# Definitivo.net
KiCad netlist of a schematic drawn in EAGLE
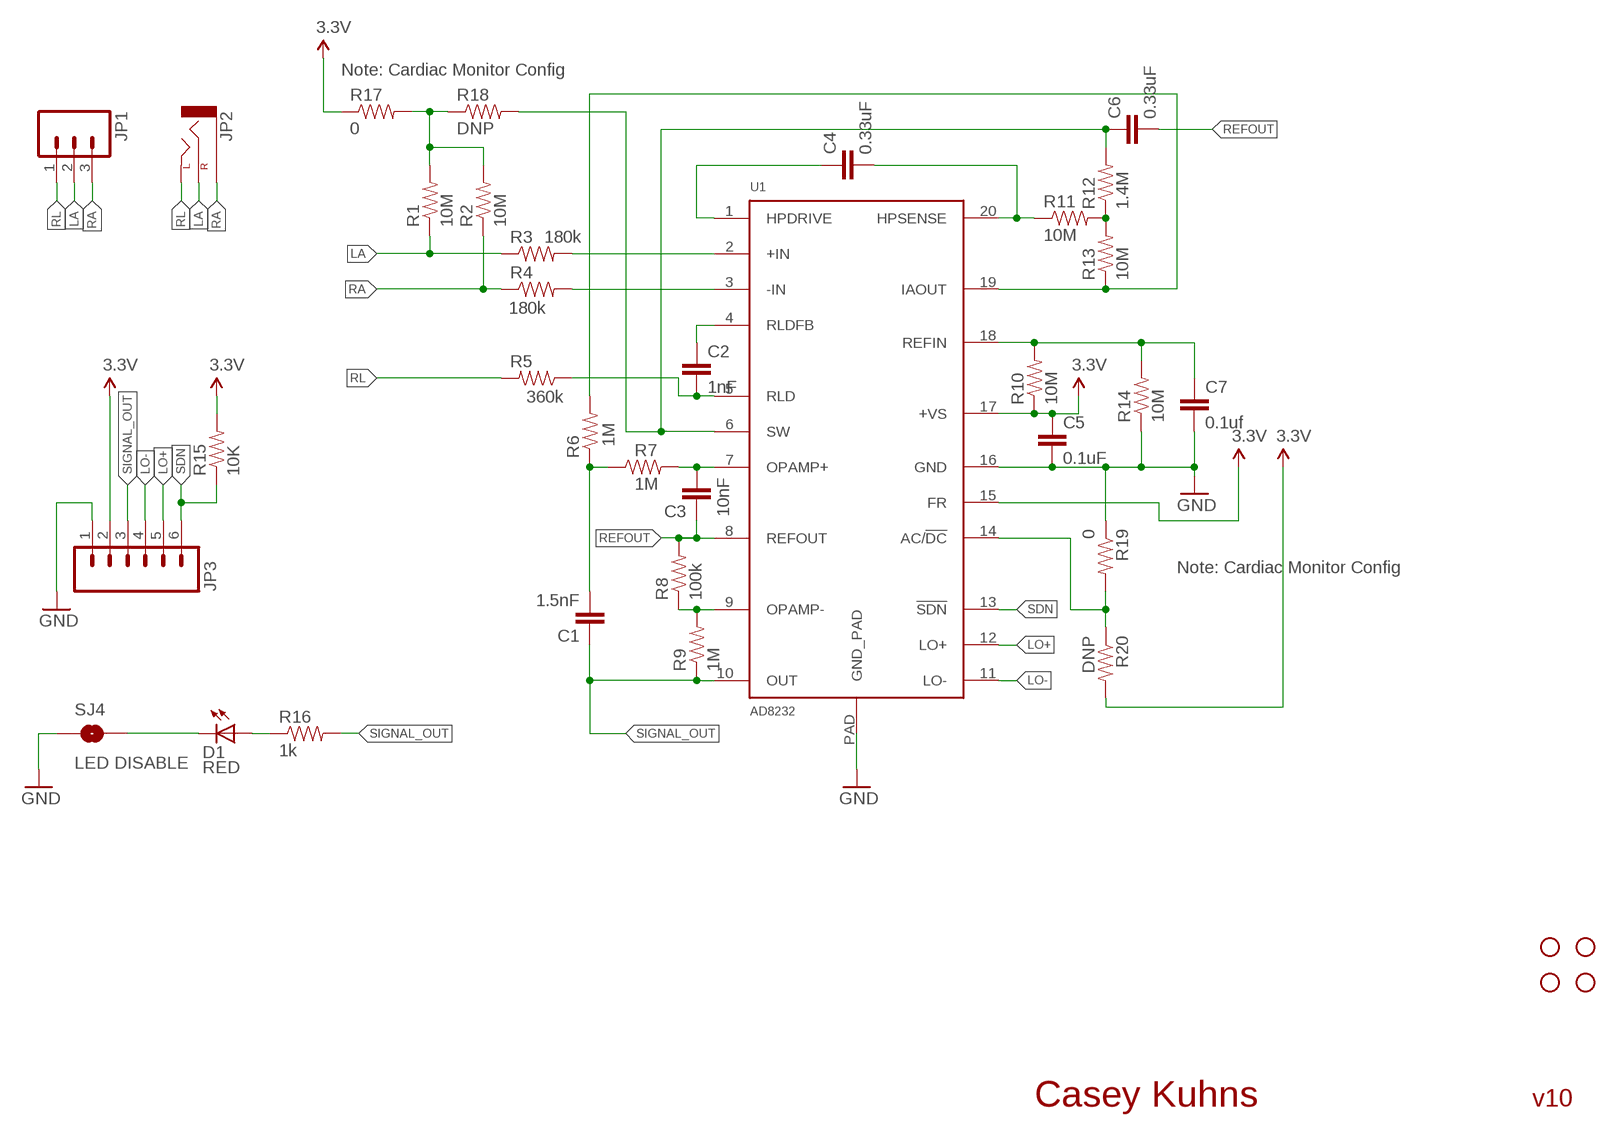
[diagram p0: schematic, sheet 1]

(export (version "E")
  (design (tool "Eeschema 10.0.6"))
  (components
    (comp (ref "C1")
      (value "1.5nF")
      (footprint "eagle-import:0603-CAP")
      (libsource (lib "eagle-import") (part "CAP0603-CAP"))
    )
    (comp (ref "C2")
      (value "1nF")
      (footprint "eagle-import:0603-CAP")
      (libsource (lib "eagle-import") (part "CAP0603-CAP"))
    )
    (comp (ref "C3")
      (value "10nF")
      (footprint "eagle-import:0603-CAP")
      (libsource (lib "eagle-import") (part "CAP0603-CAP"))
    )
    (comp (ref "C4")
      (value "0.33uF")
      (footprint "eagle-import:0805")
      (libsource (lib "eagle-import") (part "CAP0805"))
    )
    (comp (ref "C5")
      (value "0.1uF")
      (footprint "eagle-import:0603-CAP")
      (libsource (lib "eagle-import") (part "CAP0603-CAP"))
    )
    (comp (ref "C6")
      (value "0.33uF")
      (footprint "eagle-import:0805")
      (libsource (lib "eagle-import") (part "CAP0805"))
    )
    (comp (ref "C7")
      (value "0.1uf")
      (footprint "eagle-import:0603-CAP")
      (libsource (lib "eagle-import") (part "CAP0603-CAP"))
    )
    (comp (ref "D1")
      (value "RED")
      (footprint "eagle-import:LED-0603")
      (libsource (lib "eagle-import") (part "LED-RED0603"))
    )
    (comp (ref "JP1")
      (value "M03PTH")
      (footprint "eagle-import:1X03")
      (libsource (lib "eagle-import") (part "M03PTH"))
    )
    (comp (ref "JP2")
      (value "AUDIO-JACKSMD2")
      (footprint "eagle-import:AUDIO-JACK-3.5MM-SMD")
      (libsource (lib "eagle-import") (part "AUDIO-JACKSMD2"))
    )
    (comp (ref "JP3")
      (value "M06SIP")
      (footprint "eagle-import:1X06")
      (libsource (lib "eagle-import") (part "M06SIP"))
    )
    (comp (ref "R1")
      (value "10M")
      (footprint "eagle-import:0603-RES")
      (libsource (lib "eagle-import") (part "RESISTOR0603-RES"))
    )
    (comp (ref "R2")
      (value "10M")
      (footprint "eagle-import:0603-RES")
      (libsource (lib "eagle-import") (part "RESISTOR0603-RES"))
    )
    (comp (ref "R3")
      (value "180k")
      (footprint "eagle-import:0603-RES")
      (libsource (lib "eagle-import") (part "RESISTOR0603-RES"))
    )
    (comp (ref "R4")
      (value "180k")
      (footprint "eagle-import:0603-RES")
      (libsource (lib "eagle-import") (part "RESISTOR0603-RES"))
    )
    (comp (ref "R5")
      (value "360k")
      (footprint "eagle-import:0603-RES")
      (libsource (lib "eagle-import") (part "RESISTOR0603-RES"))
    )
    (comp (ref "R6")
      (value "1M")
      (footprint "eagle-import:0603-RES")
      (libsource (lib "eagle-import") (part "RESISTOR0603-RES"))
    )
    (comp (ref "R7")
      (value "1M")
      (footprint "eagle-import:0603-RES")
      (libsource (lib "eagle-import") (part "RESISTOR0603-RES"))
    )
    (comp (ref "R8")
      (value "100k")
      (footprint "eagle-import:0603-RES")
      (libsource (lib "eagle-import") (part "RESISTOR0603-RES"))
    )
    (comp (ref "R9")
      (value "1M")
      (footprint "eagle-import:0603-RES")
      (libsource (lib "eagle-import") (part "RESISTOR0603-RES"))
    )
    (comp (ref "R10")
      (value "10M")
      (footprint "eagle-import:0603-RES")
      (libsource (lib "eagle-import") (part "RESISTOR0603-RES"))
    )
    (comp (ref "R11")
      (value "10M")
      (footprint "eagle-import:0603-RES")
      (libsource (lib "eagle-import") (part "RESISTOR0603-RES"))
    )
    (comp (ref "R12")
      (value "1.4M")
      (footprint "eagle-import:0603-RES")
      (libsource (lib "eagle-import") (part "RESISTOR0603-RES"))
    )
    (comp (ref "R13")
      (value "10M")
      (footprint "eagle-import:0603-RES")
      (libsource (lib "eagle-import") (part "RESISTOR0603-RES"))
    )
    (comp (ref "R14")
      (value "10M")
      (footprint "eagle-import:0603-RES")
      (libsource (lib "eagle-import") (part "RESISTOR0603-RES"))
    )
    (comp (ref "R15")
      (value "10K")
      (footprint "eagle-import:0603-RES")
      (libsource (lib "eagle-import") (part "10KOHM1/10W1%(0603)0603"))
    )
    (comp (ref "R16")
      (value "1k")
      (footprint "eagle-import:0603-RES")
      (libsource (lib "eagle-import") (part "1K-1%"))
    )
    (comp (ref "R17")
      (value "0")
      (footprint "eagle-import:0603")
      (libsource (lib "eagle-import") (part "0OHM1/10W5%(0603)"))
    )
    (comp (ref "R18")
      (value "DNP")
      (footprint "eagle-import:0603")
      (libsource (lib "eagle-import") (part "0OHM1/10W5%(0603)"))
    )
    (comp (ref "R19")
      (value "0")
      (footprint "eagle-import:0603")
      (libsource (lib "eagle-import") (part "0OHM1/10W5%(0603)"))
    )
    (comp (ref "R20")
      (value "DNP")
      (footprint "eagle-import:0603")
      (libsource (lib "eagle-import") (part "0OHM1/10W5%(0603)"))
    )
    (comp (ref "SJ4")
      (value "LED DISABLE")
      (footprint "eagle-import:SJ_2S-TRACE")
      (libsource (lib "eagle-import") (part "SOLDERJUMPERTRACE"))
    )
    (comp (ref "STANDOFF1")
      (value "STAND-OFF")
      (footprint "eagle-import:STAND-OFF")
      (libsource (lib "eagle-import") (part "STAND-OFF"))
    )
    (comp (ref "STANDOFF2")
      (value "STAND-OFF")
      (footprint "eagle-import:STAND-OFF")
      (libsource (lib "eagle-import") (part "STAND-OFF"))
    )
    (comp (ref "STANDOFF3")
      (value "STAND-OFF")
      (footprint "eagle-import:STAND-OFF")
      (libsource (lib "eagle-import") (part "STAND-OFF"))
    )
    (comp (ref "STANDOFF4")
      (value "STAND-OFF")
      (footprint "eagle-import:STAND-OFF")
      (libsource (lib "eagle-import") (part "STAND-OFF"))
    )
    (comp (ref "U1")
      (value "AD8232")
      (footprint "eagle-import:LFCSP_20")
      (libsource (lib "eagle-import") (part "AD8232"))
    )
  )
  (nets
    (net (code "1") (name "3.3V") (class "Default")
      (node (ref "C5") (pin "1") (pinfunction "1_1") (pintype "passive"))
      (node (ref "JP3") (pin "2") (pinfunction "2_2") (pintype "passive"))
      (node (ref "R10") (pin "1") (pinfunction "1_1") (pintype "passive"))
      (node (ref "R15") (pin "2") (pinfunction "2_2") (pintype "passive"))
      (node (ref "R17") (pin "1") (pinfunction "1_1") (pintype "passive"))
      (node (ref "R20") (pin "2") (pinfunction "2_2") (pintype "passive"))
      (node (ref "U1") (pin "15") (pinfunction "FR_15") (pintype "bidirectional"))
      (node (ref "U1") (pin "17") (pinfunction "+VS_17") (pintype "bidirectional"))
    )
    (net (code "2") (name "GND") (class "Default")
      (node (ref "C5") (pin "2") (pinfunction "2_2") (pintype "passive"))
      (node (ref "C7") (pin "2") (pinfunction "2_2") (pintype "passive"))
      (node (ref "JP3") (pin "1") (pinfunction "1_1") (pintype "passive"))
      (node (ref "R14") (pin "1") (pinfunction "1_1") (pintype "passive"))
      (node (ref "R19") (pin "1") (pinfunction "1_1") (pintype "passive"))
      (node (ref "SJ4") (pin "1") (pinfunction "1_1") (pintype "passive"))
      (node (ref "U1") (pin "16") (pinfunction "GND_16") (pintype "bidirectional"))
      (node (ref "U1") (pin "PAD") (pinfunction "GND_PAD_PAD") (pintype "bidirectional"))
    )
    (net (code "3") (name "LA") (class "Default")
      (node (ref "JP1") (pin "2") (pinfunction "2_2") (pintype "passive"))
      (node (ref "JP2") (pin "RING") (pinfunction "RIGHT_RING") (pintype "bidirectional"))
      (node (ref "R1") (pin "1") (pinfunction "1_1") (pintype "passive"))
      (node (ref "R3") (pin "1") (pinfunction "1_1") (pintype "passive"))
    )
    (net (code "4") (name "LO+") (class "Default")
      (node (ref "JP3") (pin "5") (pinfunction "5_5") (pintype "passive"))
      (node (ref "U1") (pin "12") (pinfunction "LO+_12") (pintype "bidirectional"))
    )
    (net (code "5") (name "LO-") (class "Default")
      (node (ref "JP3") (pin "4") (pinfunction "4_4") (pintype "passive"))
      (node (ref "U1") (pin "11") (pinfunction "LO-_11") (pintype "bidirectional"))
    )
    (net (code "6") (name "Net-(C1-Pad2)") (class "Default")
      (node (ref "C1") (pin "2") (pinfunction "2_2") (pintype "passive"))
      (node (ref "R6") (pin "1") (pinfunction "1_1") (pintype "passive"))
      (node (ref "R7") (pin "1") (pinfunction "1_1") (pintype "passive"))
    )
    (net (code "7") (name "Net-(D1-PadA)") (class "Default")
      (node (ref "D1") (pin "A") (pinfunction "A_A") (pintype "passive"))
      (node (ref "R16") (pin "1") (pinfunction "1_1") (pintype "passive"))
    )
    (net (code "8") (name "Net-(D1-PadC)") (class "Default")
      (node (ref "D1") (pin "C") (pinfunction "C_C") (pintype "passive"))
      (node (ref "SJ4") (pin "2") (pinfunction "2_2") (pintype "passive"))
    )
    (net (code "9") (name "Net-(R1-Pad2)") (class "Default")
      (node (ref "R1") (pin "2") (pinfunction "2_2") (pintype "passive"))
      (node (ref "R17") (pin "2") (pinfunction "2_2") (pintype "passive"))
      (node (ref "R18") (pin "1") (pinfunction "1_1") (pintype "passive"))
      (node (ref "R2") (pin "2") (pinfunction "2_2") (pintype "passive"))
    )
    (net (code "10") (name "Net-(R11-Pad2)") (class "Default")
      (node (ref "R11") (pin "2") (pinfunction "2_2") (pintype "passive"))
      (node (ref "R12") (pin "1") (pinfunction "1_1") (pintype "passive"))
      (node (ref "R13") (pin "2") (pinfunction "2_2") (pintype "passive"))
    )
    (net (code "11") (name "Net-(U1-+IN)") (class "Default")
      (node (ref "R3") (pin "2") (pinfunction "2_2") (pintype "passive"))
      (node (ref "U1") (pin "2") (pinfunction "+IN_2") (pintype "bidirectional"))
    )
    (net (code "12") (name "Net-(U1--IN)") (class "Default")
      (node (ref "R4") (pin "2") (pinfunction "2_2") (pintype "passive"))
      (node (ref "U1") (pin "3") (pinfunction "-IN_3") (pintype "bidirectional"))
    )
    (net (code "13") (name "Net-(U1-AC{slash}~{DC})") (class "Default")
      (node (ref "R19") (pin "2") (pinfunction "2_2") (pintype "passive"))
      (node (ref "R20") (pin "1") (pinfunction "1_1") (pintype "passive"))
      (node (ref "U1") (pin "14") (pinfunction "AC/~{DC}_14") (pintype "bidirectional"))
    )
    (net (code "14") (name "Net-(U1-HPDRIVE)") (class "Default")
      (node (ref "C4") (pin "1") (pinfunction "1_1") (pintype "passive"))
      (node (ref "U1") (pin "1") (pinfunction "HPDRIVE_1") (pintype "bidirectional"))
    )
    (net (code "15") (name "Net-(U1-HPSENSE)") (class "Default")
      (node (ref "C4") (pin "2") (pinfunction "2_2") (pintype "passive"))
      (node (ref "R11") (pin "1") (pinfunction "1_1") (pintype "passive"))
      (node (ref "U1") (pin "20") (pinfunction "HPSENSE_20") (pintype "bidirectional"))
    )
    (net (code "16") (name "Net-(U1-IAOUT)") (class "Default")
      (node (ref "R13") (pin "1") (pinfunction "1_1") (pintype "passive"))
      (node (ref "R6") (pin "2") (pinfunction "2_2") (pintype "passive"))
      (node (ref "U1") (pin "19") (pinfunction "IAOUT_19") (pintype "bidirectional"))
    )
    (net (code "17") (name "Net-(U1-OPAMP+)") (class "Default")
      (node (ref "C3") (pin "2") (pinfunction "2_2") (pintype "passive"))
      (node (ref "R7") (pin "2") (pinfunction "2_2") (pintype "passive"))
      (node (ref "U1") (pin "7") (pinfunction "OPAMP+_7") (pintype "bidirectional"))
    )
    (net (code "18") (name "Net-(U1-OPAMP-)") (class "Default")
      (node (ref "R8") (pin "1") (pinfunction "1_1") (pintype "passive"))
      (node (ref "R9") (pin "2") (pinfunction "2_2") (pintype "passive"))
      (node (ref "U1") (pin "9") (pinfunction "OPAMP-_9") (pintype "bidirectional"))
    )
    (net (code "19") (name "Net-(U1-REFIN)") (class "Default")
      (node (ref "C7") (pin "1") (pinfunction "1_1") (pintype "passive"))
      (node (ref "R10") (pin "2") (pinfunction "2_2") (pintype "passive"))
      (node (ref "R14") (pin "2") (pinfunction "2_2") (pintype "passive"))
      (node (ref "U1") (pin "18") (pinfunction "REFIN_18") (pintype "bidirectional"))
    )
    (net (code "20") (name "Net-(U1-RLD)") (class "Default")
      (node (ref "C2") (pin "2") (pinfunction "2_2") (pintype "passive"))
      (node (ref "R5") (pin "1") (pinfunction "1_1") (pintype "passive"))
      (node (ref "U1") (pin "5") (pinfunction "RLD_5") (pintype "bidirectional"))
    )
    (net (code "21") (name "Net-(U1-RLDFB)") (class "Default")
      (node (ref "C2") (pin "1") (pinfunction "1_1") (pintype "passive"))
      (node (ref "U1") (pin "4") (pinfunction "RLDFB_4") (pintype "bidirectional"))
    )
    (net (code "22") (name "Net-(U1-SW)") (class "Default")
      (node (ref "C6") (pin "1") (pinfunction "1_1") (pintype "passive"))
      (node (ref "R12") (pin "2") (pinfunction "2_2") (pintype "passive"))
      (node (ref "R18") (pin "2") (pinfunction "2_2") (pintype "passive"))
      (node (ref "U1") (pin "6") (pinfunction "SW_6") (pintype "bidirectional"))
    )
    (net (code "23") (name "RA") (class "Default")
      (node (ref "JP1") (pin "3") (pinfunction "3_3") (pintype "passive"))
      (node (ref "JP2") (pin "SLEEVE") (pinfunction "SLEEVE_SLEEVE") (pintype "bidirectional"))
      (node (ref "R2") (pin "1") (pinfunction "1_1") (pintype "passive"))
      (node (ref "R4") (pin "1") (pinfunction "1_1") (pintype "passive"))
    )
    (net (code "24") (name "REFOUT") (class "Default")
      (node (ref "C3") (pin "1") (pinfunction "1_1") (pintype "passive"))
      (node (ref "C6") (pin "2") (pinfunction "2_2") (pintype "passive"))
      (node (ref "R8") (pin "2") (pinfunction "2_2") (pintype "passive"))
      (node (ref "U1") (pin "8") (pinfunction "REFOUT_8") (pintype "bidirectional"))
    )
    (net (code "25") (name "RL") (class "Default")
      (node (ref "JP1") (pin "1") (pinfunction "1_1") (pintype "passive"))
      (node (ref "JP2") (pin "TIP") (pinfunction "LEFT_TIP") (pintype "bidirectional"))
      (node (ref "R5") (pin "2") (pinfunction "2_2") (pintype "passive"))
    )
    (net (code "26") (name "SDN") (class "Default")
      (node (ref "JP3") (pin "6") (pinfunction "6_6") (pintype "passive"))
      (node (ref "R15") (pin "1") (pinfunction "1_1") (pintype "passive"))
      (node (ref "U1") (pin "13") (pinfunction "~{SDN}_13") (pintype "bidirectional"))
    )
    (net (code "27") (name "SIGNAL_OUT") (class "Default")
      (node (ref "C1") (pin "1") (pinfunction "1_1") (pintype "passive"))
      (node (ref "JP3") (pin "3") (pinfunction "3_3") (pintype "passive"))
      (node (ref "R16") (pin "2") (pinfunction "2_2") (pintype "passive"))
      (node (ref "R9") (pin "1") (pinfunction "1_1") (pintype "passive"))
      (node (ref "U1") (pin "10") (pinfunction "OUT_10") (pintype "bidirectional"))
    )
  )
)
